# 03_-_MCU.net
KiCad netlist of a schematic drawn in Altium Designer
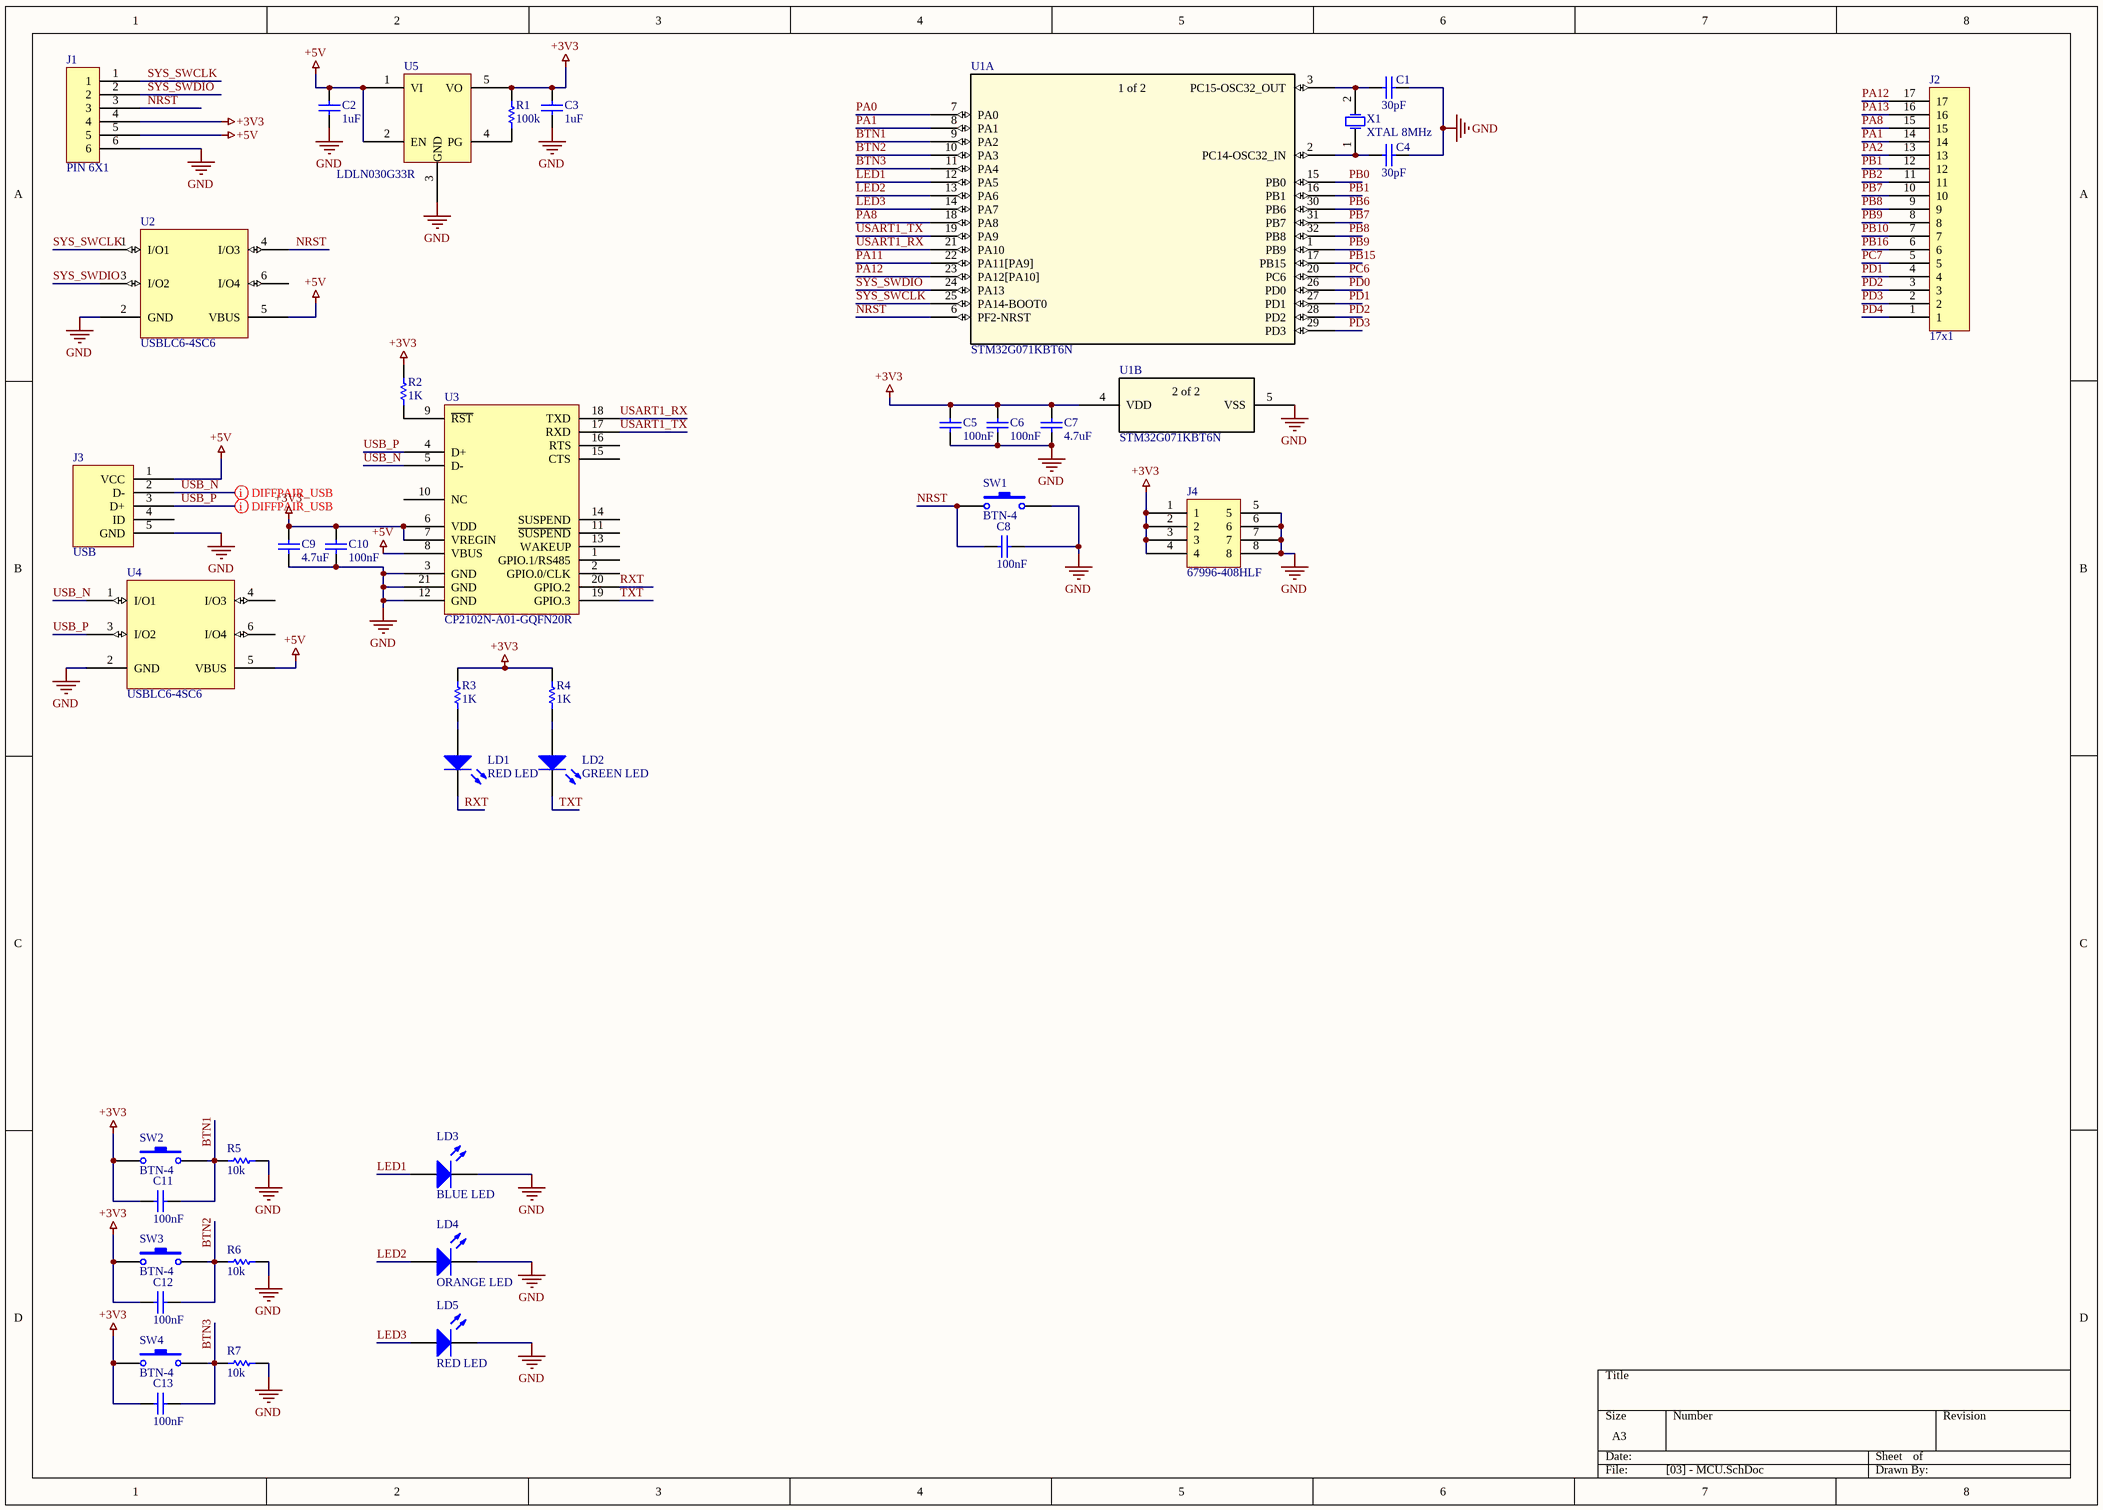
[diagram p0: [03] - MCU.SchDoc]

(export (version "E")
  (design (tool "Eeschema 10.0.6"))
  (components
    (comp (ref "C1")
      (value "30pF")
      (footprint "CAPC2012X08N")
      (description "Cap Ceramic 30pF 50V C0G 5% SMD 0805 125C Paper T/R")
      (fields
        (field (name "MANUFACTURER") "Samsung")
        (field (name "MANUFACTURER PART NUMBER") "CL21C300JBANNNC")
      )
      (libsource (lib "schLib") (part "CL21C300JBANNNC"))
    )
    (comp (ref "C2")
      (value "1uF")
      (description "Cap Ceramic 1uF 25V X7R 10% SMD 0805 125C T/R")
      (fields
        (field (name "MANUFACTURER") "Samsung")
        (field (name "MANUFACTURER PART NUMBER") "CL21B105KAFNNNE")
      )
      (libsource (lib "schLib") (part "CL21B105KAFNNNE"))
    )
    (comp (ref "C3")
      (value "1uF")
      (description "Cap Ceramic 1uF 25V X7R 10% SMD 0805 125C T/R")
      (fields
        (field (name "MANUFACTURER") "Samsung")
        (field (name "MANUFACTURER PART NUMBER") "CL21B105KAFNNNE")
      )
      (libsource (lib "schLib") (part "CL21B105KAFNNNE"))
    )
    (comp (ref "C4")
      (value "30pF")
      (footprint "CAPC2012X08N")
      (description "Cap Ceramic 30pF 50V C0G 5% SMD 0805 125C Paper T/R")
      (fields
        (field (name "MANUFACTURER") "Samsung")
        (field (name "MANUFACTURER PART NUMBER") "CL21C300JBANNNC")
      )
      (libsource (lib "schLib") (part "CL21C300JBANNNC"))
    )
    (comp (ref "C5")
      (value "100nF")
      (footprint "CAPC2012X08N")
      (description "Cap Ceramic 0.1uF 50V Y5V -20% to 80% SMD 0805 85C Paper T/R")
      (fields
        (field (name "MANUFACTURER") "Samsung")
        (field (name "MANUFACTURER PART NUMBER") "CL21F104ZBCNNNC")
      )
      (libsource (lib "schLib") (part "CL21F104ZBCNNNC"))
    )
    (comp (ref "C6")
      (value "100nF")
      (footprint "CAPC2012X08N")
      (description "Cap Ceramic 0.1uF 50V Y5V -20% to 80% SMD 0805 85C Paper T/R")
      (fields
        (field (name "MANUFACTURER") "Samsung")
        (field (name "MANUFACTURER PART NUMBER") "CL21F104ZBCNNNC")
      )
      (libsource (lib "schLib") (part "CL21F104ZBCNNNC"))
    )
    (comp (ref "C7")
      (value "4.7uF")
      (description "Cap Ceramic 4.7uF 16V X5R 10% SMD 0805 85C Embossed T/R")
      (fields
        (field (name "MANUFACTURER") "Samsung")
        (field (name "MANUFACTURER PART NUMBER") "CL21A475KOFNNNE")
      )
      (libsource (lib "schLib") (part "CL21A475KOFNNNE"))
    )
    (comp (ref "C8")
      (value "100nF")
      (footprint "CAPC2012X08N")
      (description "Cap Ceramic 0.1uF 50V Y5V -20% to 80% SMD 0805 85C Paper T/R")
      (fields
        (field (name "MANUFACTURER") "Samsung")
        (field (name "MANUFACTURER PART NUMBER") "CL21F104ZBCNNNC")
      )
      (libsource (lib "schLib") (part "CL21F104ZBCNNNC"))
    )
    (comp (ref "C9")
      (value "4.7uF")
      (description "Cap Ceramic 4.7uF 16V X5R 10% SMD 0805 85C Embossed T/R")
      (fields
        (field (name "MANUFACTURER") "Samsung")
        (field (name "MANUFACTURER PART NUMBER") "CL21A475KOFNNNE")
      )
      (libsource (lib "schLib") (part "CL21A475KOFNNNE"))
    )
    (comp (ref "C10")
      (value "100nF")
      (footprint "CAPC2012X08N")
      (description "Cap Ceramic 0.1uF 50V Y5V -20% to 80% SMD 0805 85C Paper T/R")
      (fields
        (field (name "MANUFACTURER") "Samsung")
        (field (name "MANUFACTURER PART NUMBER") "CL21F104ZBCNNNC")
      )
      (libsource (lib "schLib") (part "CL21F104ZBCNNNC"))
    )
    (comp (ref "C11")
      (value "100nF")
      (footprint "CAPC2012X08N")
      (description "Cap Ceramic 0.1uF 50V Y5V -20% to 80% SMD 0805 85C Paper T/R")
      (fields
        (field (name "MANUFACTURER") "Samsung")
        (field (name "MANUFACTURER PART NUMBER") "CL21F104ZBCNNNC")
      )
      (libsource (lib "schLib") (part "CL21F104ZBCNNNC"))
    )
    (comp (ref "C12")
      (value "100nF")
      (footprint "CAPC2012X08N")
      (description "Cap Ceramic 0.1uF 50V Y5V -20% to 80% SMD 0805 85C Paper T/R")
      (fields
        (field (name "MANUFACTURER") "Samsung")
        (field (name "MANUFACTURER PART NUMBER") "CL21F104ZBCNNNC")
      )
      (libsource (lib "schLib") (part "CL21F104ZBCNNNC"))
    )
    (comp (ref "C13")
      (value "100nF")
      (footprint "CAPC2012X08N")
      (description "Cap Ceramic 0.1uF 50V Y5V -20% to 80% SMD 0805 85C Paper T/R")
      (fields
        (field (name "MANUFACTURER") "Samsung")
        (field (name "MANUFACTURER PART NUMBER") "CL21F104ZBCNNNC")
      )
      (libsource (lib "schLib") (part "CL21F104ZBCNNNC"))
    )
    (comp (ref "J1")
      (value "PIN 6X1")
      (footprint "PIN6X1")
      (description "CONN HEADER VERT 6POS 2.54MM")
      (fields
        (field (name "MANUFACTURER") "AMP - TE CONNECTIVITY")
        (field (name "MANUFACTURER PART NUMBER") "640456-6")
      )
      (libsource (lib "schLib") (part "640456-6"))
    )
    (comp (ref "J2")
      (value "17x1")
      (footprint "PIN17X1")
      (description "CONN HEADER VERT 17POS .100 TIN")
      (fields
        (field (name "MANUFACTURER") "TE Connectivity")
        (field (name "MANUFACTURER PART NUMBER") "1-640456-7")
      )
      (libsource (lib "schLib") (part "1-640456-7"))
    )
    (comp (ref "J3")
      (value "USB")
      (footprint "AMPHENOL-usb")
      (description "CONN RCPT USB2.0 MICRO B SMD R/A")
      (fields
        (field (name "MANUFACTURER") "Amphenol FCI")
        (field (name "MANUFACTURER PART NUMBER") "10118194-0001LF")
      )
      (libsource (lib "schLib") (part "10118194-0001LF"))
    )
    (comp (ref "J4")
      (value "67996-408HLF")
      (footprint "PIN8X2")
      (description "CONN HEADER VERT 8POS 2.54MM")
      (fields (field (name "MANUFACTURER") "Amphenol FCI"))
      (libsource (lib "schLib") (part "67996-408HLF"))
    )
    (comp (ref "LD1")
      (value "RED LED")
      (footprint "LED SML")
      (description "LED RED DIFFUSED 1608 SMD")
      (fields (field (name "MANUFACTURER") "Rohm") (field (name "MANUFACTURER PART NUMBER") "SML-D12U1WT86"))
      (libsource (lib "schLib") (part "SML-D12U1WT86"))
    )
    (comp (ref "LD2")
      (value "GREEN LED")
      (footprint "LED SML")
      (description "LED YLW/GREEN DIFFUSED 1608 SMD")
      (fields (field (name "MANUFACTURER") "Rohm") (field (name "MANUFACTURER PART NUMBER") "SML-D12M1WT86"))
      (libsource (lib "schLib") (part "SML-D12M1WT86"))
    )
    (comp (ref "LD3")
      (value "BLUE LED")
      (footprint "LED APHD")
      (description "LED BLUE CLEAR 1608 SMD")
      (fields
        (field (name "MANUFACTURER") "Kingbright")
        (field (name "MANUFACTURER PART NUMBER") "APHD1608LQBC/D")
      )
      (libsource (lib "schLib") (part "APHD1608LQBC/D"))
    )
    (comp (ref "LD4")
      (value "ORANGE LED")
      (footprint "LED SML")
      (description "LED ORANGE DIFFUSED 1608 SMD")
      (fields (field (name "MANUFACTURER") "Rohm") (field (name "MANUFACTURER PART NUMBER") "SML-D12D1WT86"))
      (libsource (lib "schLib") (part "SML-D12D1WT86"))
    )
    (comp (ref "LD5")
      (value "RED LED")
      (footprint "LED SML")
      (description "LED RED DIFFUSED 1608 SMD")
      (fields (field (name "MANUFACTURER") "Rohm") (field (name "MANUFACTURER PART NUMBER") "SML-D12U1WT86"))
      (libsource (lib "schLib") (part "SML-D12U1WT86"))
    )
    (comp (ref "R1")
      (value "100k")
      (description "RES 100K OHM 1% 1/8W 0805")
      (fields
        (field (name "MANUFACTURER") "Stackpole Electronics")
        (field (name "MANUFACTURER PART NUMBER") "RMCF0805FT100K")
      )
      (libsource (lib "schLib") (part "RMCF0805FT100K"))
    )
    (comp (ref "R2")
      (value "1K")
      (description "RES 1K OHM 1% 1/4W 0805")
      (fields
        (field (name "MANUFACTURER") "Stackpole Electronics")
        (field (name "MANUFACTURER PART NUMBER") "RNCP0805FTD1K00")
      )
      (libsource (lib "schLib") (part "RNCP0805FTD1K00"))
    )
    (comp (ref "R3")
      (value "1K")
      (description "RES 1K OHM 1% 1/4W 0805")
      (fields
        (field (name "MANUFACTURER") "Stackpole Electronics")
        (field (name "MANUFACTURER PART NUMBER") "RNCP0805FTD1K00")
      )
      (libsource (lib "schLib") (part "RNCP0805FTD1K00"))
    )
    (comp (ref "R4")
      (value "1K")
      (description "RES 1K OHM 1% 1/4W 0805")
      (fields
        (field (name "MANUFACTURER") "Stackpole Electronics")
        (field (name "MANUFACTURER PART NUMBER") "RNCP0805FTD1K00")
      )
      (libsource (lib "schLib") (part "RNCP0805FTD1K00"))
    )
    (comp (ref "R5")
      (value "10k")
      (description "RES 10K OHM 1% 1/8W 0805")
      (fields
        (field (name "MANUFACTURER") "Stackpole Electronics")
        (field (name "MANUFACTURER PART NUMBER") "RMCF0805FT10K0")
      )
      (libsource (lib "schLib") (part "RMCF0805FT10K0"))
    )
    (comp (ref "R6")
      (value "10k")
      (description "RES 10K OHM 1% 1/8W 0805")
      (fields
        (field (name "MANUFACTURER") "Stackpole Electronics")
        (field (name "MANUFACTURER PART NUMBER") "RMCF0805FT10K0")
      )
      (libsource (lib "schLib") (part "RMCF0805FT10K0"))
    )
    (comp (ref "R7")
      (value "10k")
      (description "RES 10K OHM 1% 1/8W 0805")
      (fields
        (field (name "MANUFACTURER") "Stackpole Electronics")
        (field (name "MANUFACTURER PART NUMBER") "RMCF0805FT10K0")
      )
      (libsource (lib "schLib") (part "RMCF0805FT10K0"))
    )
    (comp (ref "SW1")
      (value "BTN-4")
      (footprint "PTS645")
      (description "SWITCH TACTILE SPST-NO 0.05A 12V")
      (fields
        (field (name "MANUFACTURER") "ITT C&K")
        (field (name "MANUFACTURER PART NUMBER") "PTS645SM43SMTR92LFS")
      )
      (libsource (lib "schLib") (part "PTS645SM43SMTR92LFS"))
    )
    (comp (ref "SW2")
      (value "BTN-4")
      (footprint "PTS645")
      (description "SWITCH TACTILE SPST-NO 0.05A 12V")
      (fields
        (field (name "MANUFACTURER") "ITT C&K")
        (field (name "MANUFACTURER PART NUMBER") "PTS645SM43SMTR92LFS")
      )
      (libsource (lib "schLib") (part "PTS645SM43SMTR92LFS"))
    )
    (comp (ref "SW3")
      (value "BTN-4")
      (footprint "PTS645")
      (description "SWITCH TACTILE SPST-NO 0.05A 12V")
      (fields
        (field (name "MANUFACTURER") "ITT C&K")
        (field (name "MANUFACTURER PART NUMBER") "PTS645SM43SMTR92LFS")
      )
      (libsource (lib "schLib") (part "PTS645SM43SMTR92LFS"))
    )
    (comp (ref "SW4")
      (value "BTN-4")
      (footprint "PTS645")
      (description "SWITCH TACTILE SPST-NO 0.05A 12V")
      (fields
        (field (name "MANUFACTURER") "ITT C&K")
        (field (name "MANUFACTURER PART NUMBER") "PTS645SM43SMTR92LFS")
      )
      (libsource (lib "schLib") (part "PTS645SM43SMTR92LFS"))
    )
    (comp (ref "U1")
      (value "STM32G071KBT6N")
      (footprint "LQFP-32")
      (fields
        (field (name "MANUFACTURER_PART_NUMBER") "STM32G0_LQFP32PD_T1")
        (field (name "MANUFACTURER") "STMicroelectronics")
        (field (name "COPYRIGHT") "Copyright (C) 2016 Accelerated Designs. All rights reserved")
      )
      (libsource (lib "schLib") (part "STM32G071KBT6N"))
    )
    (comp (ref "U2")
      (value "USBLC6-4SC6")
      (footprint "SOT95P280X145-6N")
      (description "TVS DIODE 5.25V 17V SOT23-6")
      (fields (field (name "MANUFACTURER") "STMicroelectronics"))
      (libsource (lib "schLib") (part "USBLC6-4SC6"))
    )
    (comp (ref "U3")
      (value "CP2102N-A01-GQFN20R")
      (footprint "*SILABS_QFN20")
      (description "IC BRIDGE USB TO UART 20QFN")
      (fields (field (name "MANUFACTURER") "Silicon Labs"))
      (libsource (lib "schLib") (part "CP2102N-A01-GQFN20R"))
    )
    (comp (ref "U4")
      (value "USBLC6-4SC6")
      (footprint "SOT95P280X145-6N")
      (description "TVS DIODE 5.25V 17V SOT23-6")
      (fields (field (name "MANUFACTURER") "STMicroelectronics"))
      (libsource (lib "schLib") (part "USBLC6-4SC6"))
    )
    (comp (ref "U5")
      (value "LDLN030G33R")
      (footprint "SOT95P280X100-5N")
      (description "IC REG LIN 3.3V 300MA TSOT23-5")
      (fields (field (name "MANUFACTURER") "STMicroelectronics"))
      (libsource (lib "schLib") (part "LDLN030G33R"))
    )
    (comp (ref "X1")
      (value "XTAL 8MHz")
      (footprint "HC-49S")
      (description "CRYSTAL 8.0000MHZ 18PF SMD")
      (fields (field (name "MANUFACTURER") "TXC") (field (name "MANUFACTURER PART NUMBER") "9C-8.000MEEJ-T"))
      (libsource (lib "schLib") (part "9C-8.000MEEJ-T"))
    )
  )
  (nets
    (net (code "1") (name "+3V3") (class "Default")
      (node (ref "C10") (pin "2") (pinfunction "2_2") (pintype "passive"))
      (node (ref "C11") (pin "2") (pinfunction "2_2") (pintype "passive"))
      (node (ref "C12") (pin "2") (pinfunction "2_2") (pintype "passive"))
      (node (ref "C13") (pin "2") (pinfunction "2_2") (pintype "passive"))
      (node (ref "C3") (pin "2") (pinfunction "2_2") (pintype "passive"))
      (node (ref "C5") (pin "2") (pinfunction "2_2") (pintype "passive"))
      (node (ref "C6") (pin "2") (pinfunction "2_2") (pintype "passive"))
      (node (ref "C7") (pin "2") (pinfunction "2_2") (pintype "passive"))
      (node (ref "C9") (pin "2") (pinfunction "2_2") (pintype "passive"))
      (node (ref "J1") (pin "4") (pinfunction "4_4") (pintype "passive"))
      (node (ref "J4") (pin "1") (pinfunction "1_1") (pintype "passive"))
      (node (ref "J4") (pin "2") (pinfunction "2_2") (pintype "passive"))
      (node (ref "J4") (pin "3") (pinfunction "3_3") (pintype "passive"))
      (node (ref "J4") (pin "4") (pinfunction "4_4") (pintype "passive"))
      (node (ref "R1") (pin "2") (pinfunction "2_2") (pintype "passive"))
      (node (ref "R2") (pin "2") (pinfunction "2_2") (pintype "passive"))
      (node (ref "R3") (pin "1") (pinfunction "1_1") (pintype "passive"))
      (node (ref "R4") (pin "1") (pinfunction "1_1") (pintype "passive"))
      (node (ref "SW2") (pin "1") (pinfunction "1_1") (pintype "passive"))
      (node (ref "SW3") (pin "1") (pinfunction "1_1") (pintype "passive"))
      (node (ref "SW4") (pin "1") (pinfunction "1_1") (pintype "passive"))
      (node (ref "U1") (pin "4") (pinfunction "VDD_4") (pintype "power_in"))
      (node (ref "U3") (pin "6") (pinfunction "VDD_6") (pintype "passive"))
      (node (ref "U3") (pin "7") (pinfunction "VREGIN_7") (pintype "passive"))
      (node (ref "U5") (pin "5") (pinfunction "VO_5") (pintype "passive"))
    )
    (net (code "2") (name "+5V") (class "Default")
      (node (ref "C2") (pin "2") (pinfunction "2_2") (pintype "passive"))
      (node (ref "J1") (pin "5") (pinfunction "5_5") (pintype "passive"))
      (node (ref "J3") (pin "1") (pinfunction "VCC_1") (pintype "passive"))
      (node (ref "U2") (pin "5") (pinfunction "VBUS_5") (pintype "power_in"))
      (node (ref "U3") (pin "8") (pinfunction "VBUS_8") (pintype "passive"))
      (node (ref "U4") (pin "5") (pinfunction "VBUS_5") (pintype "power_in"))
      (node (ref "U5") (pin "1") (pinfunction "VI_1") (pintype "passive"))
      (node (ref "U5") (pin "2") (pinfunction "EN_2") (pintype "passive"))
    )
    (net (code "3") (name "/BTN1") (class "Default")
      (node (ref "C11") (pin "1") (pinfunction "1_1") (pintype "passive"))
      (node (ref "R5") (pin "1") (pinfunction "1_1") (pintype "passive"))
      (node (ref "SW2") (pin "2") (pinfunction "2_2") (pintype "passive"))
      (node (ref "U1") (pin "9") (pinfunction "PA2_9") (pintype "bidirectional"))
    )
    (net (code "4") (name "/BTN2") (class "Default")
      (node (ref "C12") (pin "1") (pinfunction "1_1") (pintype "passive"))
      (node (ref "R6") (pin "1") (pinfunction "1_1") (pintype "passive"))
      (node (ref "SW3") (pin "2") (pinfunction "2_2") (pintype "passive"))
      (node (ref "U1") (pin "10") (pinfunction "PA3_10") (pintype "bidirectional"))
    )
    (net (code "5") (name "/BTN3") (class "Default")
      (node (ref "C13") (pin "1") (pinfunction "1_1") (pintype "passive"))
      (node (ref "R7") (pin "1") (pinfunction "1_1") (pintype "passive"))
      (node (ref "SW4") (pin "2") (pinfunction "2_2") (pintype "passive"))
      (node (ref "U1") (pin "11") (pinfunction "PA4_11") (pintype "bidirectional"))
    )
    (net (code "6") (name "/LED1") (class "Default")
      (node (ref "LD3") (pin "1") (pinfunction "A_1") (pintype "passive"))
      (node (ref "U1") (pin "12") (pinfunction "PA5_12") (pintype "bidirectional"))
    )
    (net (code "7") (name "/LED2") (class "Default")
      (node (ref "LD4") (pin "1") (pinfunction "A_1") (pintype "passive"))
      (node (ref "U1") (pin "13") (pinfunction "PA6_13") (pintype "bidirectional"))
    )
    (net (code "8") (name "/LED3") (class "Default")
      (node (ref "LD5") (pin "1") (pinfunction "A_1") (pintype "passive"))
      (node (ref "U1") (pin "14") (pinfunction "PA7_14") (pintype "bidirectional"))
    )
    (net (code "9") (name "/NRST") (class "Default")
      (node (ref "C8") (pin "2") (pinfunction "2_2") (pintype "passive"))
      (node (ref "J1") (pin "3") (pinfunction "3_3") (pintype "passive"))
      (node (ref "SW1") (pin "1") (pinfunction "1_1") (pintype "passive"))
      (node (ref "U1") (pin "6") (pinfunction "PF2-NRST_6") (pintype "bidirectional"))
      (node (ref "U2") (pin "4") (pinfunction "I/O3_4") (pintype "bidirectional"))
    )
    (net (code "10") (name "/PA0") (class "Default")
      (node (ref "U1") (pin "7") (pinfunction "PA0_7") (pintype "bidirectional"))
    )
    (net (code "11") (name "/PA1") (class "Default")
      (node (ref "J2") (pin "14") (pinfunction "14_14") (pintype "passive"))
      (node (ref "U1") (pin "8") (pinfunction "PA1_8") (pintype "bidirectional"))
    )
    (net (code "12") (name "/PA2") (class "Default")
      (node (ref "J2") (pin "13") (pinfunction "13_13") (pintype "passive"))
    )
    (net (code "13") (name "/PA8") (class "Default")
      (node (ref "J2") (pin "15") (pinfunction "15_15") (pintype "passive"))
      (node (ref "U1") (pin "18") (pinfunction "PA8_18") (pintype "bidirectional"))
    )
    (net (code "14") (name "/PA11") (class "Default")
      (node (ref "U1") (pin "22") (pinfunction "PA11[PA9]_22") (pintype "bidirectional"))
    )
    (net (code "15") (name "/PA12") (class "Default")
      (node (ref "J2") (pin "17") (pinfunction "17_17") (pintype "passive"))
      (node (ref "U1") (pin "23") (pinfunction "PA12[PA10]_23") (pintype "bidirectional"))
    )
    (net (code "16") (name "/PA13") (class "Default")
      (node (ref "J2") (pin "16") (pinfunction "16_16") (pintype "passive"))
    )
    (net (code "17") (name "/PB0") (class "Default")
      (node (ref "U1") (pin "15") (pinfunction "PB0_15") (pintype "bidirectional"))
    )
    (net (code "18") (name "/PB1") (class "Default")
      (node (ref "J2") (pin "12") (pinfunction "12_12") (pintype "passive"))
      (node (ref "U1") (pin "16") (pinfunction "PB1_16") (pintype "bidirectional"))
    )
    (net (code "19") (name "/PB2") (class "Default")
      (node (ref "J2") (pin "11") (pinfunction "11_11") (pintype "passive"))
    )
    (net (code "20") (name "/PB6") (class "Default")
      (node (ref "U1") (pin "30") (pinfunction "PB6_30") (pintype "bidirectional"))
    )
    (net (code "21") (name "/PB7") (class "Default")
      (node (ref "J2") (pin "10") (pinfunction "10_10") (pintype "passive"))
      (node (ref "U1") (pin "31") (pinfunction "PB7_31") (pintype "bidirectional"))
    )
    (net (code "22") (name "/PB8") (class "Default")
      (node (ref "J2") (pin "9") (pinfunction "9_9") (pintype "passive"))
      (node (ref "U1") (pin "32") (pinfunction "PB8_32") (pintype "bidirectional"))
    )
    (net (code "23") (name "/PB9") (class "Default")
      (node (ref "J2") (pin "8") (pinfunction "8_8") (pintype "passive"))
      (node (ref "U1") (pin "1") (pinfunction "PB9_1") (pintype "bidirectional"))
    )
    (net (code "24") (name "/PB10") (class "Default")
      (node (ref "J2") (pin "7") (pinfunction "7_7") (pintype "passive"))
    )
    (net (code "25") (name "/PB15") (class "Default")
      (node (ref "U1") (pin "17") (pinfunction "PB15_17") (pintype "bidirectional"))
    )
    (net (code "26") (name "/PB16") (class "Default")
      (node (ref "J2") (pin "6") (pinfunction "6_6") (pintype "passive"))
    )
    (net (code "27") (name "/PC6") (class "Default")
      (node (ref "U1") (pin "20") (pinfunction "PC6_20") (pintype "bidirectional"))
    )
    (net (code "28") (name "/PC7") (class "Default")
      (node (ref "J2") (pin "5") (pinfunction "5_5") (pintype "passive"))
    )
    (net (code "29") (name "/PD0") (class "Default")
      (node (ref "U1") (pin "26") (pinfunction "PD0_26") (pintype "bidirectional"))
    )
    (net (code "30") (name "/PD1") (class "Default")
      (node (ref "J2") (pin "4") (pinfunction "4_4") (pintype "passive"))
      (node (ref "U1") (pin "27") (pinfunction "PD1_27") (pintype "bidirectional"))
    )
    (net (code "31") (name "/PD2") (class "Default")
      (node (ref "J2") (pin "3") (pinfunction "3_3") (pintype "passive"))
      (node (ref "U1") (pin "28") (pinfunction "PD2_28") (pintype "bidirectional"))
    )
    (net (code "32") (name "/PD3") (class "Default")
      (node (ref "J2") (pin "2") (pinfunction "2_2") (pintype "passive"))
      (node (ref "U1") (pin "29") (pinfunction "PD3_29") (pintype "bidirectional"))
    )
    (net (code "33") (name "/PD4") (class "Default")
      (node (ref "J2") (pin "1") (pinfunction "1_1") (pintype "passive"))
    )
    (net (code "34") (name "/RXT") (class "Default")
      (node (ref "LD1") (pin "2") (pinfunction "K_2") (pintype "passive"))
      (node (ref "U3") (pin "20") (pinfunction "GPIO.2_20") (pintype "passive"))
    )
    (net (code "35") (name "/SYS_SWCLK") (class "Default")
      (node (ref "J1") (pin "1") (pinfunction "1_1") (pintype "passive"))
      (node (ref "U1") (pin "25") (pinfunction "PA14-BOOT0_25") (pintype "bidirectional"))
      (node (ref "U2") (pin "1") (pinfunction "I/O1_1") (pintype "bidirectional"))
    )
    (net (code "36") (name "/SYS_SWDIO") (class "Default")
      (node (ref "J1") (pin "2") (pinfunction "2_2") (pintype "passive"))
      (node (ref "U1") (pin "24") (pinfunction "PA13_24") (pintype "bidirectional"))
      (node (ref "U2") (pin "3") (pinfunction "I/O2_3") (pintype "bidirectional"))
    )
    (net (code "37") (name "/TXT") (class "Default")
      (node (ref "LD2") (pin "2") (pinfunction "K_2") (pintype "passive"))
      (node (ref "U3") (pin "19") (pinfunction "GPIO.3_19") (pintype "passive"))
    )
    (net (code "38") (name "/USART1_RX") (class "Default")
      (node (ref "U1") (pin "21") (pinfunction "PA10_21") (pintype "bidirectional"))
      (node (ref "U3") (pin "18") (pinfunction "TXD_18") (pintype "passive"))
    )
    (net (code "39") (name "/USART1_TX") (class "Default")
      (node (ref "U1") (pin "19") (pinfunction "PA9_19") (pintype "bidirectional"))
      (node (ref "U3") (pin "17") (pinfunction "RXD_17") (pintype "passive"))
    )
    (net (code "40") (name "/USB_N") (class "Default")
      (node (ref "J3") (pin "2") (pinfunction "D-_2") (pintype "passive"))
      (node (ref "U3") (pin "5") (pinfunction "D-_5") (pintype "passive"))
      (node (ref "U4") (pin "1") (pinfunction "I/O1_1") (pintype "bidirectional"))
    )
    (net (code "41") (name "/USB_P") (class "Default")
      (node (ref "J3") (pin "3") (pinfunction "D+_3") (pintype "passive"))
      (node (ref "U3") (pin "4") (pinfunction "D+_4") (pintype "passive"))
      (node (ref "U4") (pin "3") (pinfunction "I/O2_3") (pintype "bidirectional"))
    )
    (net (code "42") (name "GND") (class "Default")
      (node (ref "C1") (pin "2") (pinfunction "2_2") (pintype "passive"))
      (node (ref "C10") (pin "1") (pinfunction "1_1") (pintype "passive"))
      (node (ref "C2") (pin "1") (pinfunction "1_1") (pintype "passive"))
      (node (ref "C3") (pin "1") (pinfunction "1_1") (pintype "passive"))
      (node (ref "C4") (pin "2") (pinfunction "2_2") (pintype "passive"))
      (node (ref "C5") (pin "1") (pinfunction "1_1") (pintype "passive"))
      (node (ref "C6") (pin "1") (pinfunction "1_1") (pintype "passive"))
      (node (ref "C7") (pin "1") (pinfunction "1_1") (pintype "passive"))
      (node (ref "C8") (pin "1") (pinfunction "1_1") (pintype "passive"))
      (node (ref "C9") (pin "1") (pinfunction "1_1") (pintype "passive"))
      (node (ref "J1") (pin "6") (pinfunction "6_6") (pintype "passive"))
      (node (ref "J3") (pin "5") (pinfunction "GND_5") (pintype "passive"))
      (node (ref "J4") (pin "5") (pinfunction "5_5") (pintype "passive"))
      (node (ref "J4") (pin "6") (pinfunction "6_6") (pintype "passive"))
      (node (ref "J4") (pin "7") (pinfunction "7_7") (pintype "passive"))
      (node (ref "J4") (pin "8") (pinfunction "8_8") (pintype "passive"))
      (node (ref "LD3") (pin "2") (pinfunction "K_2") (pintype "passive"))
      (node (ref "LD4") (pin "2") (pinfunction "K_2") (pintype "passive"))
      (node (ref "LD5") (pin "2") (pinfunction "K_2") (pintype "passive"))
      (node (ref "R5") (pin "2") (pinfunction "2_2") (pintype "passive"))
      (node (ref "R6") (pin "2") (pinfunction "2_2") (pintype "passive"))
      (node (ref "R7") (pin "2") (pinfunction "2_2") (pintype "passive"))
      (node (ref "SW1") (pin "2") (pinfunction "2_2") (pintype "passive"))
      (node (ref "U1") (pin "5") (pinfunction "VSS_5") (pintype "power_in"))
      (node (ref "U2") (pin "2") (pinfunction "GND_2") (pintype "power_in"))
      (node (ref "U3") (pin "12") (pinfunction "GND_12") (pintype "passive"))
      (node (ref "U3") (pin "21") (pinfunction "GND_21") (pintype "passive"))
      (node (ref "U3") (pin "3") (pinfunction "GND_3") (pintype "passive"))
      (node (ref "U4") (pin "2") (pinfunction "GND_2") (pintype "power_in"))
      (node (ref "U5") (pin "3") (pinfunction "GND_3") (pintype "passive"))
    )
    (net (code "43") (name "Net-(LD1-A)") (class "Default")
      (node (ref "LD1") (pin "1") (pinfunction "A_1") (pintype "passive"))
      (node (ref "R3") (pin "2") (pinfunction "2_2") (pintype "passive"))
    )
    (net (code "44") (name "Net-(LD2-A)") (class "Default")
      (node (ref "LD2") (pin "1") (pinfunction "A_1") (pintype "passive"))
      (node (ref "R4") (pin "2") (pinfunction "2_2") (pintype "passive"))
    )
    (net (code "45") (name "Net-(U1A-PC14-OSC32_IN)") (class "Default")
      (node (ref "C4") (pin "1") (pinfunction "1_1") (pintype "passive"))
      (node (ref "U1") (pin "2") (pinfunction "PC14-OSC32_IN_2") (pintype "bidirectional"))
      (node (ref "X1") (pin "1") (pinfunction "OSC1_1") (pintype "passive"))
    )
    (net (code "46") (name "Net-(U1A-PC15-OSC32_OUT)") (class "Default")
      (node (ref "C1") (pin "1") (pinfunction "1_1") (pintype "passive"))
      (node (ref "U1") (pin "3") (pinfunction "PC15-OSC32_OUT_3") (pintype "bidirectional"))
      (node (ref "X1") (pin "2") (pinfunction "OSC2_2") (pintype "passive"))
    )
    (net (code "47") (name "Net-(U3-~{RST})") (class "Default")
      (node (ref "R2") (pin "1") (pinfunction "1_1") (pintype "passive"))
      (node (ref "U3") (pin "9") (pinfunction "~{RST}_9") (pintype "passive"))
    )
    (net (code "48") (name "Net-(U5-PG)") (class "Default")
      (node (ref "R1") (pin "1") (pinfunction "1_1") (pintype "passive"))
      (node (ref "U5") (pin "4") (pinfunction "PG_4") (pintype "passive"))
    )
    (net (code "49") (name "unconnected-(J3-ID-Pad4)") (class "Default")
      (node (ref "J3") (pin "4") (pinfunction "ID_4") (pintype "passive"))
    )
    (net (code "50") (name "unconnected-(U2-I{slash}O4-Pad6)") (class "Default")
      (node (ref "U2") (pin "6") (pinfunction "I/O4_6") (pintype "bidirectional"))
    )
    (net (code "51") (name "unconnected-(U3-CTS-Pad15)") (class "Default")
      (node (ref "U3") (pin "15") (pinfunction "CTS_15") (pintype "passive"))
    )
    (net (code "52") (name "unconnected-(U3-GPIO.0{slash}CLK-Pad2)") (class "Default")
      (node (ref "U3") (pin "2") (pinfunction "GPIO.0/CLK_2") (pintype "passive"))
    )
    (net (code "53") (name "unconnected-(U3-GPIO.1{slash}RS485-Pad1)") (class "Default")
      (node (ref "U3") (pin "1") (pinfunction "GPIO.1/RS485_1") (pintype "passive"))
    )
    (net (code "54") (name "unconnected-(U3-NC-Pad10)") (class "Default")
      (node (ref "U3") (pin "10") (pinfunction "NC_10") (pintype "passive"))
    )
    (net (code "55") (name "unconnected-(U3-RTS-Pad16)") (class "Default")
      (node (ref "U3") (pin "16") (pinfunction "RTS_16") (pintype "passive"))
    )
    (net (code "56") (name "unconnected-(U3-SUSPEND-Pad14)") (class "Default")
      (node (ref "U3") (pin "14") (pinfunction "SUSPEND_14") (pintype "passive"))
    )
    (net (code "57") (name "unconnected-(U3-WAKEUP-Pad13)") (class "Default")
      (node (ref "U3") (pin "13") (pinfunction "WAKEUP_13") (pintype "passive"))
    )
    (net (code "58") (name "unconnected-(U3-~{SUSPEND}-Pad11)") (class "Default")
      (node (ref "U3") (pin "11") (pinfunction "~{SUSPEND}_11") (pintype "passive"))
    )
    (net (code "59") (name "unconnected-(U4-I{slash}O3-Pad4)") (class "Default")
      (node (ref "U4") (pin "4") (pinfunction "I/O3_4") (pintype "bidirectional"))
    )
    (net (code "60") (name "unconnected-(U4-I{slash}O4-Pad6)") (class "Default")
      (node (ref "U4") (pin "6") (pinfunction "I/O4_6") (pintype "bidirectional"))
    )
  )
)
